# neogeo2tg16_12.net
KiCad netlist of a schematic drawn in EAGLE
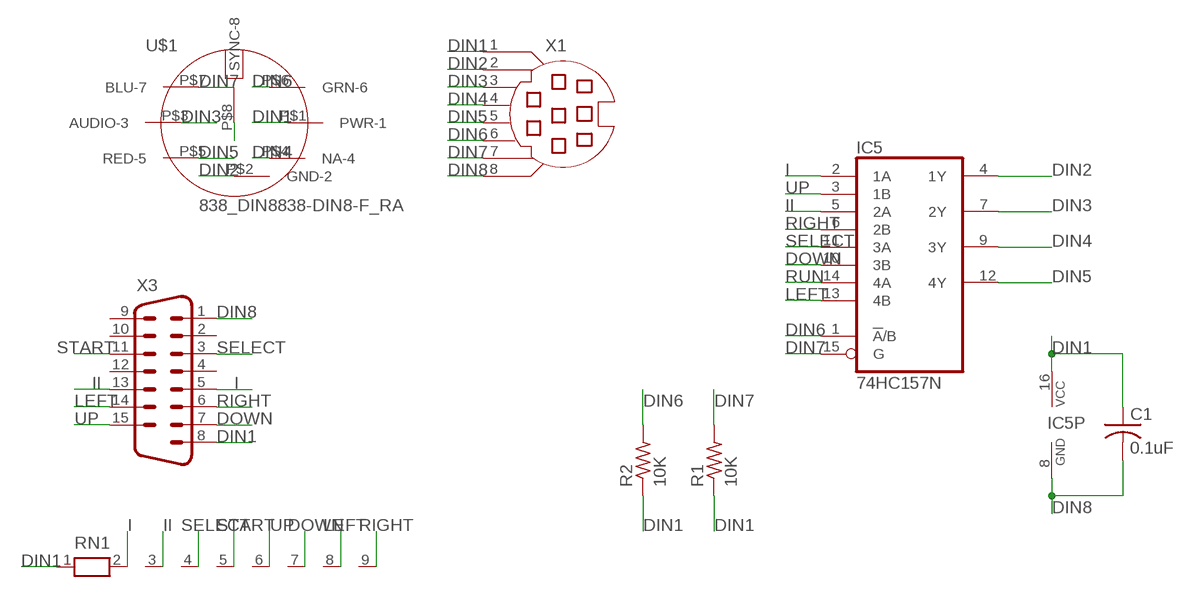
[diagram p0: schematic, sheet 1]

(export (version "E")
  (design (tool "Eeschema 10.0.6"))
  (components
    (comp (ref "C1")
      (value "0.1uF")
      (footprint "eagle-import:C025-024X044")
      (libsource (lib "eagle-import") (part "C-US025-024X044"))
    )
    (comp (ref "IC5")
      (value "74HC157N")
      (footprint "eagle-import:DIL16")
      (libsource (lib "eagle-import") (part "74157NHC"))
    )
    (comp (ref "R1")
      (value "10K")
      (footprint "eagle-import:0204_7")
      (libsource (lib "eagle-import") (part "R-US_0204/7"))
    )
    (comp (ref "R2")
      (value "10K")
      (footprint "eagle-import:0204_7")
      (libsource (lib "eagle-import") (part "R-US_0204/7"))
    )
    (comp (ref "RN1")
      (value "RN08")
      (footprint "eagle-import:RN-9")
      (libsource (lib "eagle-import") (part "RN08"))
    )
    (comp (ref "U$1")
      (value "838_DIN8838-DIN8-F_RA")
      (footprint "eagle-import:838_DIN8")
      (libsource (lib "eagle-import") (part "838_DIN8838-DIN8-F_RA"))
    )
    (comp (ref "X1")
      (value "MD08SS")
      (footprint "eagle-import:MDIN08SS")
      (libsource (lib "eagle-import") (part "MD08SS"))
    )
    (comp (ref "X3")
      (value "M15HP")
      (footprint "eagle-import:M15HP")
      (libsource (lib "eagle-import") (part "M15HP"))
    )
  )
  (nets
    (net (code "1") (name "/DIN1") (class "Default")
      (node (ref "C1") (pin "1") (pinfunction "1_1") (pintype "passive"))
      (node (ref "IC5") (pin "16") (pinfunction "VCC_16") (pintype "power_in"))
      (node (ref "R1") (pin "1") (pinfunction "1_1") (pintype "passive"))
      (node (ref "R2") (pin "1") (pinfunction "1_1") (pintype "passive"))
      (node (ref "RN1") (pin "1") (pinfunction "1_1") (pintype "passive"))
      (node (ref "U$1") (pin "P$1") (pinfunction "PWR-1_P$1") (pintype "power_in"))
      (node (ref "X1") (pin "1") (pinfunction "1_1") (pintype "passive"))
      (node (ref "X3") (pin "8") (pinfunction "8_8") (pintype "passive"))
    )
    (net (code "2") (name "/DIN2") (class "Default")
      (node (ref "IC5") (pin "4") (pinfunction "1Y_4") (pintype "output"))
      (node (ref "U$1") (pin "P$2") (pinfunction "GND-2_P$2") (pintype "bidirectional"))
      (node (ref "X1") (pin "2") (pinfunction "2_2") (pintype "passive"))
    )
    (net (code "3") (name "/DIN3") (class "Default")
      (node (ref "IC5") (pin "7") (pinfunction "2Y_7") (pintype "output"))
      (node (ref "U$1") (pin "P$3") (pinfunction "AUDIO-3_P$3") (pintype "bidirectional"))
      (node (ref "X1") (pin "3") (pinfunction "3_3") (pintype "passive"))
    )
    (net (code "4") (name "/DIN4") (class "Default")
      (node (ref "IC5") (pin "9") (pinfunction "3Y_9") (pintype "output"))
      (node (ref "U$1") (pin "P$4") (pinfunction "NA-4_P$4") (pintype "bidirectional"))
      (node (ref "X1") (pin "4") (pinfunction "4_4") (pintype "passive"))
    )
    (net (code "5") (name "/DIN5") (class "Default")
      (node (ref "IC5") (pin "12") (pinfunction "4Y_12") (pintype "output"))
      (node (ref "U$1") (pin "P$5") (pinfunction "RED-5_P$5") (pintype "bidirectional"))
      (node (ref "X1") (pin "5") (pinfunction "5_5") (pintype "passive"))
    )
    (net (code "6") (name "/DIN6") (class "Default")
      (node (ref "IC5") (pin "1") (pinfunction "~{A}/B_1") (pintype "input"))
      (node (ref "R2") (pin "2") (pinfunction "2_2") (pintype "passive"))
      (node (ref "U$1") (pin "P$6") (pinfunction "GRN-6_P$6") (pintype "bidirectional"))
      (node (ref "X1") (pin "6") (pinfunction "6_6") (pintype "passive"))
    )
    (net (code "7") (name "/DIN7") (class "Default")
      (node (ref "IC5") (pin "15") (pinfunction "G_15") (pintype "input"))
      (node (ref "R1") (pin "2") (pinfunction "2_2") (pintype "passive"))
      (node (ref "U$1") (pin "P$7") (pinfunction "BLU-7_P$7") (pintype "bidirectional"))
      (node (ref "X1") (pin "7") (pinfunction "7_7") (pintype "passive"))
    )
    (net (code "8") (name "/DIN8") (class "Default")
      (node (ref "C1") (pin "2") (pinfunction "2_2") (pintype "passive"))
      (node (ref "IC5") (pin "8") (pinfunction "GND_8") (pintype "power_in"))
      (node (ref "U$1") (pin "P$8") (pinfunction "SYNC-8_P$8") (pintype "bidirectional"))
      (node (ref "X1") (pin "8") (pinfunction "8_8") (pintype "passive"))
      (node (ref "X3") (pin "1") (pinfunction "1_1") (pintype "passive"))
    )
    (net (code "9") (name "/DOWN") (class "Default")
      (node (ref "IC5") (pin "10") (pinfunction "3B_10") (pintype "input"))
      (node (ref "RN1") (pin "7") (pinfunction "7_7") (pintype "passive"))
      (node (ref "X3") (pin "7") (pinfunction "7_7") (pintype "passive"))
    )
    (net (code "10") (name "/I") (class "Default")
      (node (ref "IC5") (pin "2") (pinfunction "1A_2") (pintype "input"))
      (node (ref "RN1") (pin "2") (pinfunction "2_2") (pintype "passive"))
      (node (ref "X3") (pin "5") (pinfunction "5_5") (pintype "passive"))
    )
    (net (code "11") (name "/II") (class "Default")
      (node (ref "IC5") (pin "5") (pinfunction "2A_5") (pintype "input"))
      (node (ref "RN1") (pin "3") (pinfunction "3_3") (pintype "passive"))
      (node (ref "X3") (pin "13") (pinfunction "13_13") (pintype "passive"))
    )
    (net (code "12") (name "/LEFT") (class "Default")
      (node (ref "IC5") (pin "13") (pinfunction "4B_13") (pintype "input"))
      (node (ref "RN1") (pin "8") (pinfunction "8_8") (pintype "passive"))
      (node (ref "X3") (pin "14") (pinfunction "14_14") (pintype "passive"))
    )
    (net (code "13") (name "/RIGHT") (class "Default")
      (node (ref "IC5") (pin "6") (pinfunction "2B_6") (pintype "input"))
      (node (ref "RN1") (pin "9") (pinfunction "9_9") (pintype "passive"))
      (node (ref "X3") (pin "6") (pinfunction "6_6") (pintype "passive"))
    )
    (net (code "14") (name "/RUN") (class "Default")
      (node (ref "IC5") (pin "14") (pinfunction "4A_14") (pintype "input"))
    )
    (net (code "15") (name "/SELECT") (class "Default")
      (node (ref "IC5") (pin "11") (pinfunction "3A_11") (pintype "input"))
      (node (ref "RN1") (pin "4") (pinfunction "4_4") (pintype "passive"))
      (node (ref "X3") (pin "3") (pinfunction "3_3") (pintype "passive"))
    )
    (net (code "16") (name "/START") (class "Default")
      (node (ref "RN1") (pin "5") (pinfunction "5_5") (pintype "passive"))
      (node (ref "X3") (pin "11") (pinfunction "11_11") (pintype "passive"))
    )
    (net (code "17") (name "/UP") (class "Default")
      (node (ref "IC5") (pin "3") (pinfunction "1B_3") (pintype "input"))
      (node (ref "RN1") (pin "6") (pinfunction "6_6") (pintype "passive"))
      (node (ref "X3") (pin "15") (pinfunction "15_15") (pintype "passive"))
    )
    (net (code "18") (name "unconnected-(X3-Pad2)") (class "Default")
      (node (ref "X3") (pin "2") (pinfunction "2_2") (pintype "passive"))
    )
    (net (code "19") (name "unconnected-(X3-Pad4)") (class "Default")
      (node (ref "X3") (pin "4") (pinfunction "4_4") (pintype "passive"))
    )
    (net (code "20") (name "unconnected-(X3-Pad9)") (class "Default")
      (node (ref "X3") (pin "9") (pinfunction "9_9") (pintype "passive"))
    )
    (net (code "21") (name "unconnected-(X3-Pad10)") (class "Default")
      (node (ref "X3") (pin "10") (pinfunction "10_10") (pintype "passive"))
    )
    (net (code "22") (name "unconnected-(X3-Pad12)") (class "Default")
      (node (ref "X3") (pin "12") (pinfunction "12_12") (pintype "passive"))
    )
  )
)
